# MODUL_CAN_V100.net
KiCad netlist of a schematic drawn in EAGLE
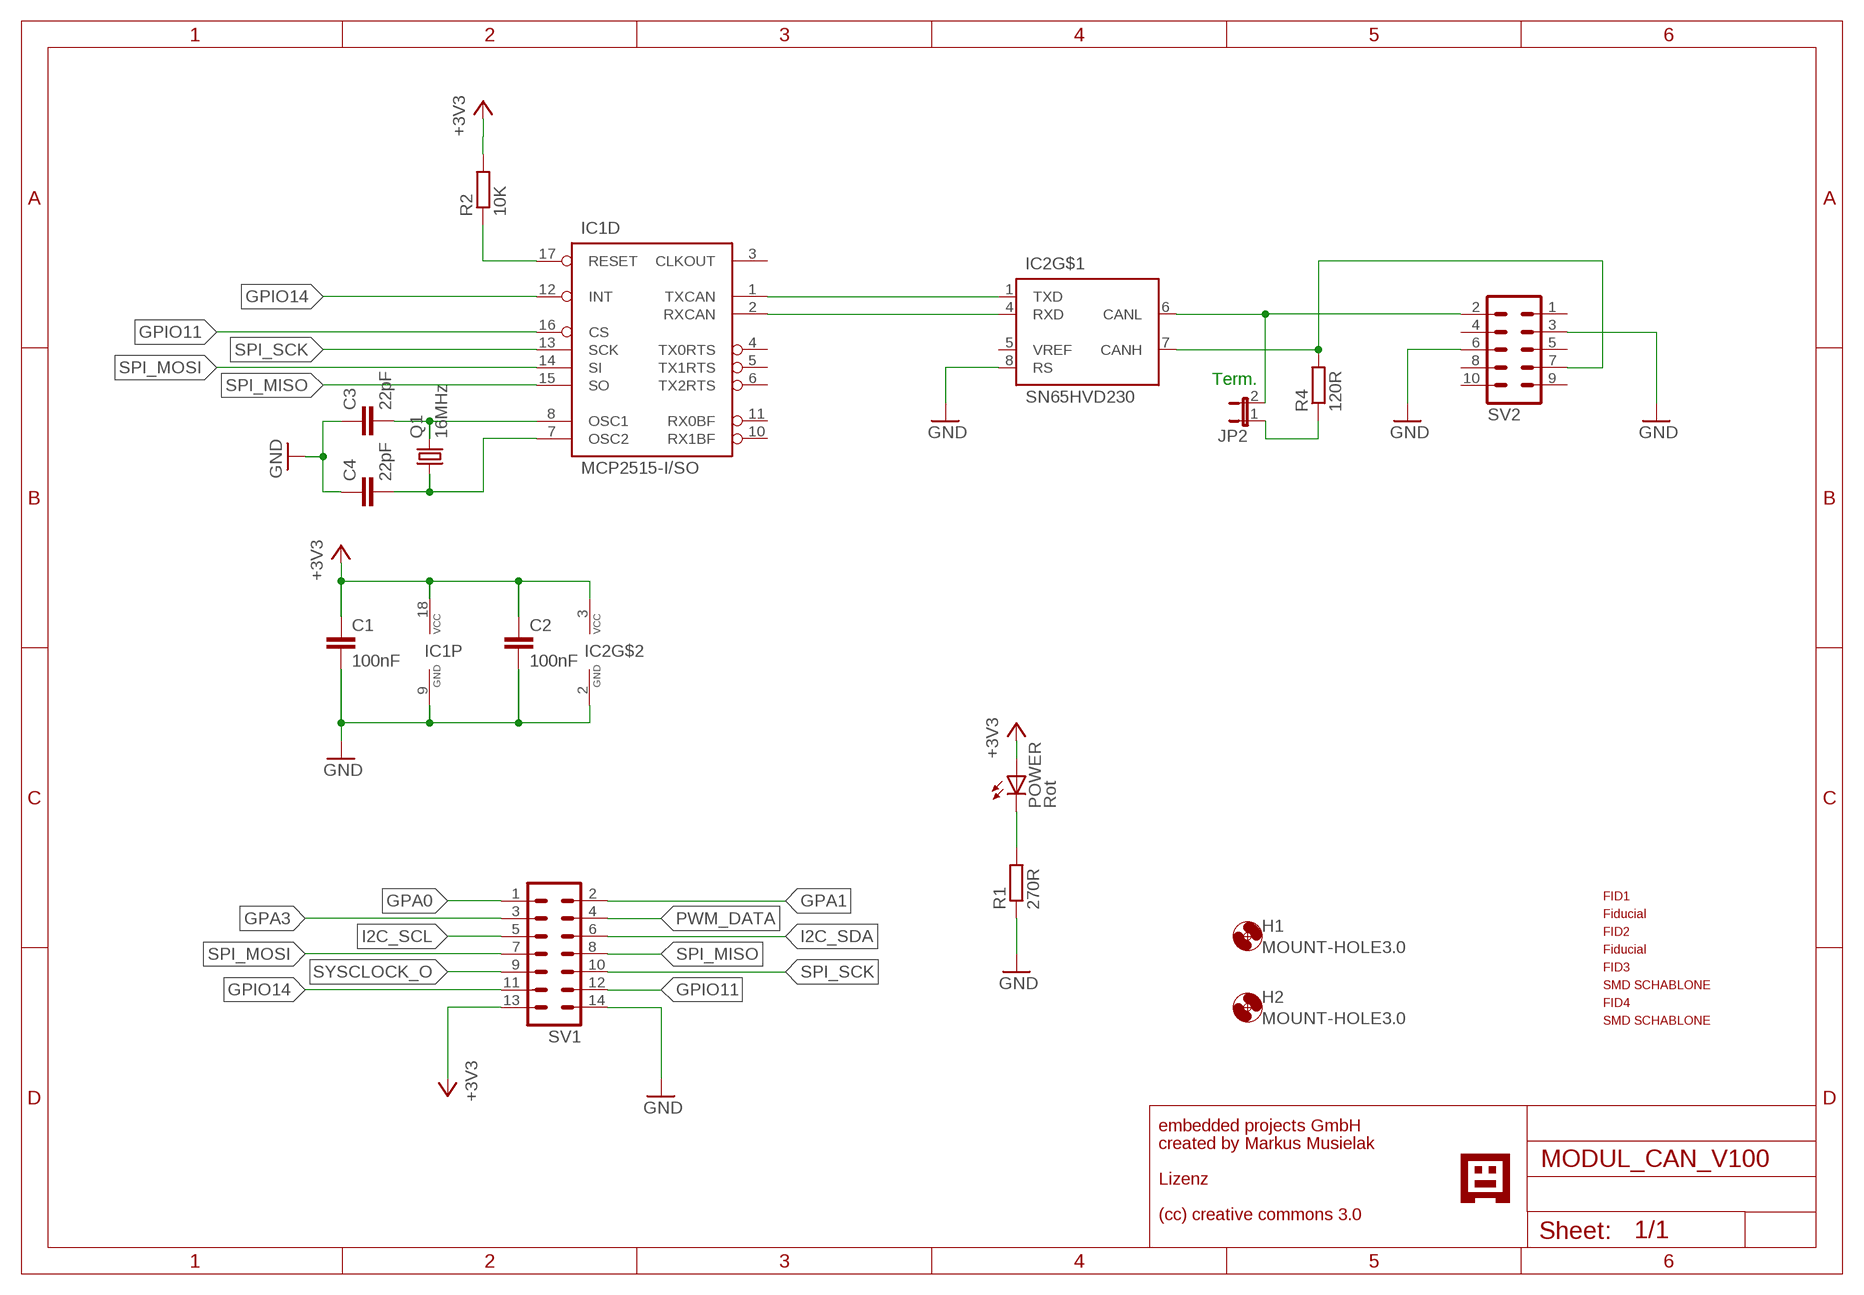
[diagram p0: schematic, sheet 1]

(export (version "E")
  (design (tool "Eeschema 10.0.6"))
  (components
    (comp (ref "C1")
      (value "100nF")
      (footprint "eagle-import:C0805")
      (libsource (lib "eagle-import") (part "C-EUC0805"))
    )
    (comp (ref "C2")
      (value "100nF")
      (footprint "eagle-import:C0805")
      (libsource (lib "eagle-import") (part "C-EUC0805"))
    )
    (comp (ref "C3")
      (value "22pF")
      (footprint "eagle-import:C0805")
      (libsource (lib "eagle-import") (part "C-EUC0805"))
    )
    (comp (ref "C4")
      (value "22pF")
      (footprint "eagle-import:C0805")
      (libsource (lib "eagle-import") (part "C-EUC0805"))
    )
    (comp (ref "FID1")
      (value "PASSERMARKEN_FIDUCIAL")
      (footprint "eagle-import:PASSERMARKEN_FIDUCIAL")
      (libsource (lib "eagle-import") (part "PASSERMARKEN_FIDUCIAL"))
    )
    (comp (ref "FID2")
      (value "PASSERMARKEN_FIDUCIAL")
      (footprint "eagle-import:PASSERMARKEN_FIDUCIAL")
      (libsource (lib "eagle-import") (part "PASSERMARKEN_FIDUCIAL"))
    )
    (comp (ref "FID3")
      (value "PASSERMARKEN_FIDUCIAL")
      (footprint "eagle-import:PASSERMARKEN_FIDUCIAL")
      (libsource (lib "eagle-import") (part "SMDSCHABLONE_PASSERMARKEN_FIDUCIAL"))
    )
    (comp (ref "FID4")
      (value "PASSERMARKEN_FIDUCIAL")
      (footprint "eagle-import:PASSERMARKEN_FIDUCIAL")
      (libsource (lib "eagle-import") (part "SMDSCHABLONE_PASSERMARKEN_FIDUCIAL"))
    )
    (comp (ref "H1")
      (value "MOUNT-HOLE3.0")
      (footprint "eagle-import:3,0")
      (libsource (lib "eagle-import") (part "MOUNT-HOLE3.0"))
    )
    (comp (ref "H2")
      (value "MOUNT-HOLE3.0")
      (footprint "eagle-import:3,0")
      (libsource (lib "eagle-import") (part "MOUNT-HOLE3.0"))
    )
    (comp (ref "IC1")
      (value "MCP2515-I/SO")
      (footprint "eagle-import:SO-18W")
      (fields (field (name "FARNELL") "1292239"))
      (libsource (lib "eagle-import") (part "MCP2515SO"))
    )
    (comp (ref "IC2")
      (value "SN65HVD230")
      (footprint "eagle-import:SO08")
      (fields (field (name "FARNELL") "1103105"))
      (libsource (lib "eagle-import") (part "MCP2551SO8"))
    )
    (comp (ref "JP2")
      (value "JP1E")
      (footprint "eagle-import:JP1")
      (libsource (lib "eagle-import") (part "JP1E"))
    )
    (comp (ref "POWER")
      (value "Rot")
      (footprint "eagle-import:CHIP-LED0805")
      (libsource (lib "eagle-import") (part "LEDCHIP-LED0805"))
    )
    (comp (ref "Q1")
      (value "16MHz")
      (footprint "eagle-import:HC49UP")
      (libsource (lib "eagle-import") (part "CRYSTALHC49UP"))
    )
    (comp (ref "R1")
      (value "270R")
      (footprint "eagle-import:R0805")
      (libsource (lib "eagle-import") (part "R-EU_R0805"))
    )
    (comp (ref "R2")
      (value "10K")
      (footprint "eagle-import:R0805")
      (libsource (lib "eagle-import") (part "R-EU_R0805"))
    )
    (comp (ref "R4")
      (value "120R")
      (footprint "eagle-import:R0805")
      (libsource (lib "eagle-import") (part "R-EU_R0805"))
    )
    (comp (ref "SV1")
      (value "ML14")
      (footprint "eagle-import:ML14")
      (libsource (lib "eagle-import") (part "ML14"))
    )
    (comp (ref "SV2")
      (value "ML10")
      (footprint "eagle-import:ML10")
      (libsource (lib "eagle-import") (part "ML10"))
    )
    (comp (ref "U$2")
      (value "GNUBLINLOGOSIEB")
      (footprint "eagle-import:GNUSIEBDRUCK")
      (libsource (lib "eagle-import") (part "GNUBLINLOGOSIEB"))
    )
  )
  (nets
    (net (code "1") (name "+3V3") (class "Default")
      (node (ref "C1") (pin "1") (pinfunction "1_1") (pintype "passive"))
      (node (ref "C2") (pin "1") (pinfunction "1_1") (pintype "passive"))
      (node (ref "IC1") (pin "18") (pinfunction "VCC_18") (pintype "power_in"))
      (node (ref "IC2") (pin "3") (pinfunction "VCC_3") (pintype "power_in"))
      (node (ref "POWER") (pin "A") (pinfunction "A_A") (pintype "passive"))
      (node (ref "R2") (pin "2") (pinfunction "2_2") (pintype "passive"))
      (node (ref "SV1") (pin "13") (pinfunction "13_13") (pintype "passive"))
    )
    (net (code "2") (name "GND") (class "Default")
      (node (ref "C1") (pin "2") (pinfunction "2_2") (pintype "passive"))
      (node (ref "C2") (pin "2") (pinfunction "2_2") (pintype "passive"))
      (node (ref "C3") (pin "1") (pinfunction "1_1") (pintype "passive"))
      (node (ref "C4") (pin "1") (pinfunction "1_1") (pintype "passive"))
      (node (ref "IC1") (pin "9") (pinfunction "GND_9") (pintype "power_in"))
      (node (ref "IC2") (pin "2") (pinfunction "GND_2") (pintype "power_in"))
      (node (ref "IC2") (pin "8") (pinfunction "RS_8") (pintype "bidirectional"))
      (node (ref "R1") (pin "1") (pinfunction "1_1") (pintype "passive"))
      (node (ref "SV1") (pin "14") (pinfunction "14_14") (pintype "passive"))
      (node (ref "SV2") (pin "3") (pinfunction "3_3") (pintype "passive"))
      (node (ref "SV2") (pin "6") (pinfunction "6_6") (pintype "passive"))
    )
    (net (code "3") (name "GPA0") (class "Default")
      (node (ref "SV1") (pin "1") (pinfunction "1_1") (pintype "passive"))
    )
    (net (code "4") (name "GPA1") (class "Default")
      (node (ref "SV1") (pin "2") (pinfunction "2_2") (pintype "passive"))
    )
    (net (code "5") (name "GPA3") (class "Default")
      (node (ref "SV1") (pin "3") (pinfunction "3_3") (pintype "passive"))
    )
    (net (code "6") (name "GPIO11") (class "Default")
      (node (ref "IC1") (pin "16") (pinfunction "CS_16") (pintype "input"))
      (node (ref "SV1") (pin "12") (pinfunction "12_12") (pintype "passive"))
    )
    (net (code "7") (name "GPIO14") (class "Default")
      (node (ref "IC1") (pin "12") (pinfunction "INT_12") (pintype "output"))
      (node (ref "SV1") (pin "11") (pinfunction "11_11") (pintype "passive"))
    )
    (net (code "8") (name "I2C_SCL") (class "Default")
      (node (ref "SV1") (pin "5") (pinfunction "5_5") (pintype "passive"))
    )
    (net (code "9") (name "I2C_SDA") (class "Default")
      (node (ref "SV1") (pin "6") (pinfunction "6_6") (pintype "passive"))
    )
    (net (code "10") (name "Net-(IC1A-OSC1)") (class "Default")
      (node (ref "C3") (pin "2") (pinfunction "2_2") (pintype "passive"))
      (node (ref "IC1") (pin "8") (pinfunction "OSC1_8") (pintype "input"))
      (node (ref "Q1") (pin "2") (pinfunction "2_2") (pintype "passive"))
    )
    (net (code "11") (name "Net-(IC1A-OSC2)") (class "Default")
      (node (ref "C4") (pin "2") (pinfunction "2_2") (pintype "passive"))
      (node (ref "IC1") (pin "7") (pinfunction "OSC2_7") (pintype "input"))
      (node (ref "Q1") (pin "1") (pinfunction "1_1") (pintype "passive"))
    )
    (net (code "12") (name "Net-(IC1A-RESET)") (class "Default")
      (node (ref "IC1") (pin "17") (pinfunction "RESET_17") (pintype "input"))
      (node (ref "R2") (pin "1") (pinfunction "1_1") (pintype "passive"))
    )
    (net (code "13") (name "Net-(IC1A-RXCAN)") (class "Default")
      (node (ref "IC1") (pin "2") (pinfunction "RXCAN_2") (pintype "input"))
      (node (ref "IC2") (pin "4") (pinfunction "RXD_4") (pintype "bidirectional"))
    )
    (net (code "14") (name "Net-(IC1A-TXCAN)") (class "Default")
      (node (ref "IC1") (pin "1") (pinfunction "TXCAN_1") (pintype "output"))
      (node (ref "IC2") (pin "1") (pinfunction "TXD_1") (pintype "bidirectional"))
    )
    (net (code "15") (name "Net-(IC2A-CANH)") (class "Default")
      (node (ref "IC2") (pin "7") (pinfunction "CANH_7") (pintype "bidirectional"))
      (node (ref "R4") (pin "2") (pinfunction "2_2") (pintype "passive"))
      (node (ref "SV2") (pin "7") (pinfunction "7_7") (pintype "passive"))
    )
    (net (code "16") (name "Net-(IC2A-CANL)") (class "Default")
      (node (ref "IC2") (pin "6") (pinfunction "CANL_6") (pintype "bidirectional"))
      (node (ref "JP2") (pin "2") (pinfunction "2_2") (pintype "passive"))
      (node (ref "SV2") (pin "2") (pinfunction "2_2") (pintype "passive"))
    )
    (net (code "17") (name "Net-(JP2-Pad1)") (class "Default")
      (node (ref "JP2") (pin "1") (pinfunction "1_1") (pintype "passive"))
      (node (ref "R4") (pin "1") (pinfunction "1_1") (pintype "passive"))
    )
    (net (code "18") (name "Net-(POWER-PadC)") (class "Default")
      (node (ref "POWER") (pin "C") (pinfunction "C_C") (pintype "passive"))
      (node (ref "R1") (pin "2") (pinfunction "2_2") (pintype "passive"))
    )
    (net (code "19") (name "PWM_DATA") (class "Default")
      (node (ref "SV1") (pin "4") (pinfunction "4_4") (pintype "passive"))
    )
    (net (code "20") (name "SPI_MISO") (class "Default")
      (node (ref "IC1") (pin "15") (pinfunction "SO_15") (pintype "output"))
      (node (ref "SV1") (pin "8") (pinfunction "8_8") (pintype "passive"))
    )
    (net (code "21") (name "SPI_MOSI") (class "Default")
      (node (ref "IC1") (pin "14") (pinfunction "SI_14") (pintype "input"))
      (node (ref "SV1") (pin "7") (pinfunction "7_7") (pintype "passive"))
    )
    (net (code "22") (name "SPI_SCK") (class "Default")
      (node (ref "IC1") (pin "13") (pinfunction "SCK_13") (pintype "input"))
      (node (ref "SV1") (pin "10") (pinfunction "10_10") (pintype "passive"))
    )
    (net (code "23") (name "SYSCLOCK_O") (class "Default")
      (node (ref "SV1") (pin "9") (pinfunction "9_9") (pintype "passive"))
    )
    (net (code "24") (name "unconnected-(IC1A-CLKOUT-Pad3)") (class "Default")
      (node (ref "IC1") (pin "3") (pinfunction "CLKOUT_3") (pintype "output"))
    )
    (net (code "25") (name "unconnected-(IC1A-RX0BF-Pad11)") (class "Default")
      (node (ref "IC1") (pin "11") (pinfunction "RX0BF_11") (pintype "output"))
    )
    (net (code "26") (name "unconnected-(IC1A-RX1BF-Pad10)") (class "Default")
      (node (ref "IC1") (pin "10") (pinfunction "RX1BF_10") (pintype "output"))
    )
    (net (code "27") (name "unconnected-(IC1A-TX0RTS-Pad4)") (class "Default")
      (node (ref "IC1") (pin "4") (pinfunction "TX0RTS_4") (pintype "input"))
    )
    (net (code "28") (name "unconnected-(IC1A-TX1RTS-Pad5)") (class "Default")
      (node (ref "IC1") (pin "5") (pinfunction "TX1RTS_5") (pintype "input"))
    )
    (net (code "29") (name "unconnected-(IC1A-TX2RTS-Pad6)") (class "Default")
      (node (ref "IC1") (pin "6") (pinfunction "TX2RTS_6") (pintype "input"))
    )
    (net (code "30") (name "unconnected-(IC2A-VREF-Pad5)") (class "Default")
      (node (ref "IC2") (pin "5") (pinfunction "VREF_5") (pintype "bidirectional"))
    )
    (net (code "31") (name "unconnected-(SV2-Pad1)") (class "Default")
      (node (ref "SV2") (pin "1") (pinfunction "1_1") (pintype "passive"))
    )
    (net (code "32") (name "unconnected-(SV2-Pad4)") (class "Default")
      (node (ref "SV2") (pin "4") (pinfunction "4_4") (pintype "passive"))
    )
    (net (code "33") (name "unconnected-(SV2-Pad5)") (class "Default")
      (node (ref "SV2") (pin "5") (pinfunction "5_5") (pintype "passive"))
    )
    (net (code "34") (name "unconnected-(SV2-Pad8)") (class "Default")
      (node (ref "SV2") (pin "8") (pinfunction "8_8") (pintype "passive"))
    )
    (net (code "35") (name "unconnected-(SV2-Pad9)") (class "Default")
      (node (ref "SV2") (pin "9") (pinfunction "9_9") (pintype "passive"))
    )
    (net (code "36") (name "unconnected-(SV2-Pad10)") (class "Default")
      (node (ref "SV2") (pin "10") (pinfunction "10_10") (pintype "passive"))
    )
  )
)
